# SCH_attempt2_2024-01-23.net
KiCad netlist of a schematic drawn in EasyEDA
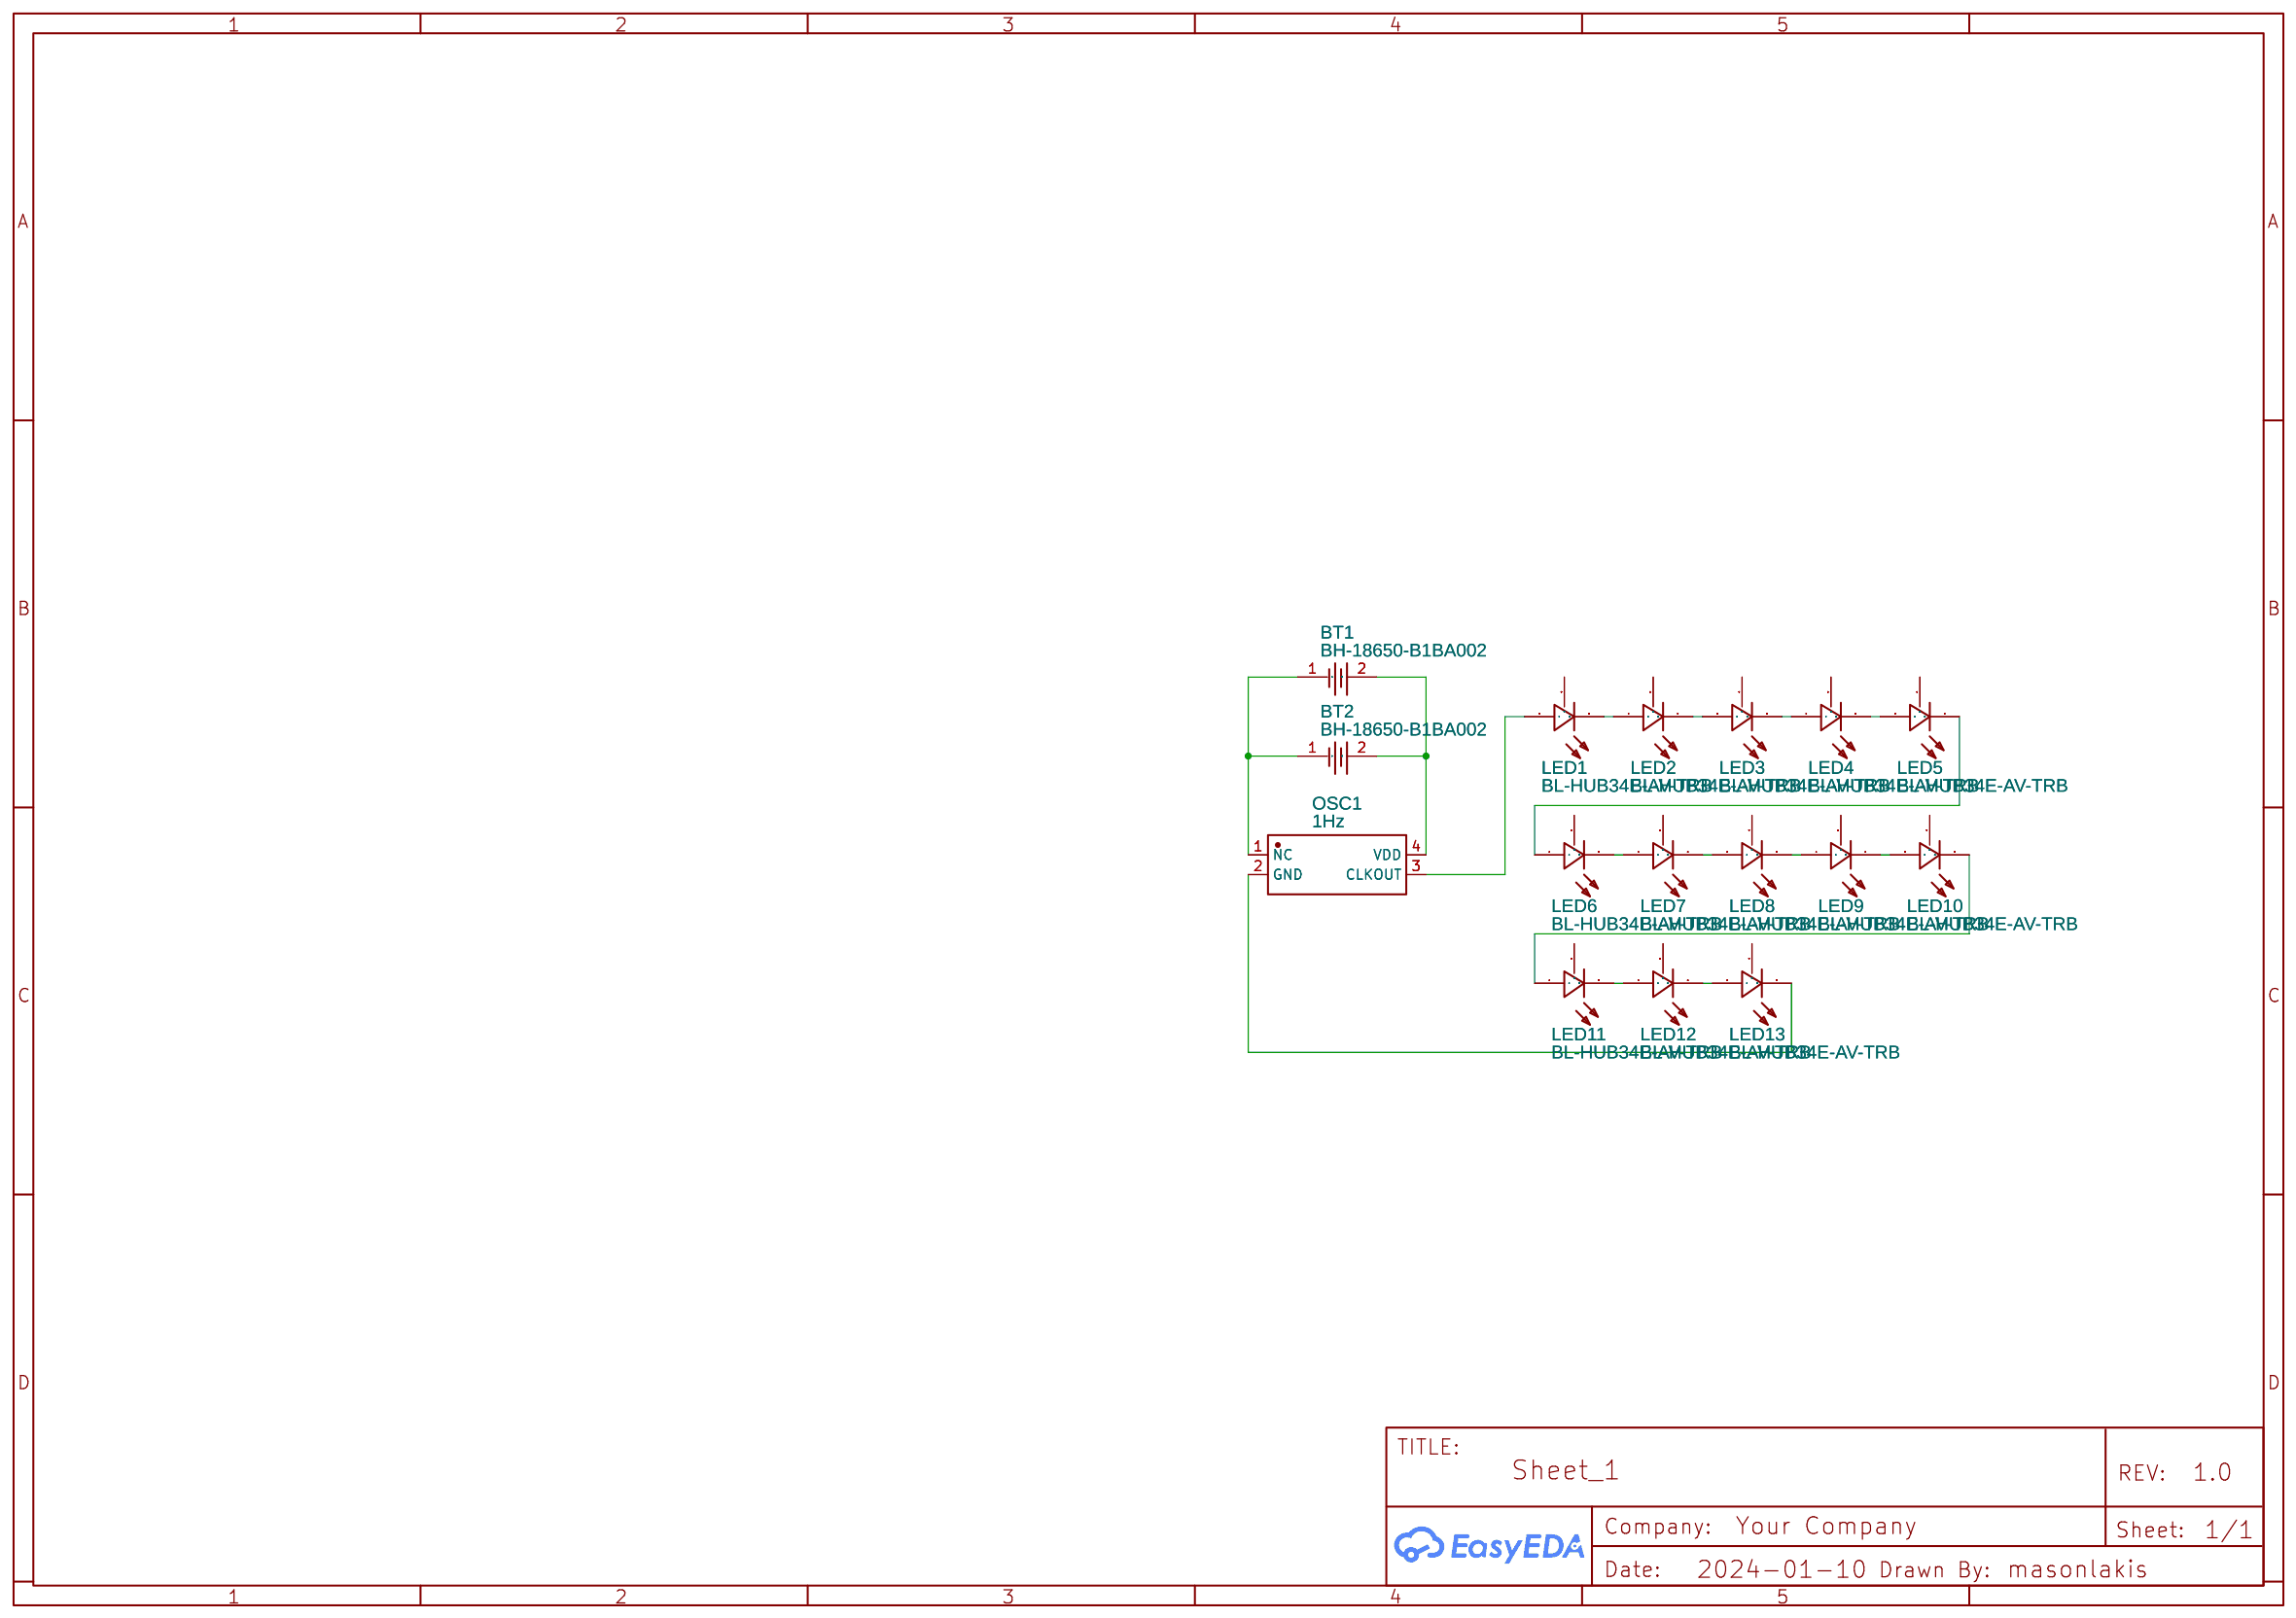
[diagram p0: schematic sheet]

(export (version "E")
  (design (tool "Eeschema 10.0.6"))
  (components
    (comp (ref "BT1")
      (value "BH-18650-B1BA002")
      (fields (field (name "Manufacturer") "MYOUNG(美阳)"))
      (libsource (lib "") (part "BH-18650-B1BA002"))
    )
    (comp (ref "BT2")
      (value "BH-18650-B1BA002")
      (fields (field (name "Manufacturer") "MYOUNG(美阳)"))
      (libsource (lib "") (part "BH-18650-B1BA002"))
    )
    (comp (ref "LED1")
      (value "BL-HUB34E-AV-TRB")
      (fields (field (name "Manufacturer") "BrtLed(佰鸿)"))
      (libsource (lib "") (part "BL-HUB34E-AV-TRB"))
    )
    (comp (ref "LED2")
      (value "BL-HUB34E-AV-TRB")
      (fields (field (name "Manufacturer") "BrtLed(佰鸿)"))
      (libsource (lib "") (part "BL-HUB34E-AV-TRB"))
    )
    (comp (ref "LED3")
      (value "BL-HUB34E-AV-TRB")
      (fields (field (name "Manufacturer") "BrtLed(佰鸿)"))
      (libsource (lib "") (part "BL-HUB34E-AV-TRB"))
    )
    (comp (ref "LED4")
      (value "BL-HUB34E-AV-TRB")
      (fields (field (name "Manufacturer") "BrtLed(佰鸿)"))
      (libsource (lib "") (part "BL-HUB34E-AV-TRB"))
    )
    (comp (ref "LED5")
      (value "BL-HUB34E-AV-TRB")
      (fields (field (name "Manufacturer") "BrtLed(佰鸿)"))
      (libsource (lib "") (part "BL-HUB34E-AV-TRB"))
    )
    (comp (ref "LED6")
      (value "BL-HUB34E-AV-TRB")
      (fields (field (name "Manufacturer") "BrtLed(佰鸿)"))
      (libsource (lib "") (part "BL-HUB34E-AV-TRB"))
    )
    (comp (ref "LED7")
      (value "BL-HUB34E-AV-TRB")
      (fields (field (name "Manufacturer") "BrtLed(佰鸿)"))
      (libsource (lib "") (part "BL-HUB34E-AV-TRB"))
    )
    (comp (ref "LED8")
      (value "BL-HUB34E-AV-TRB")
      (fields (field (name "Manufacturer") "BrtLed(佰鸿)"))
      (libsource (lib "") (part "BL-HUB34E-AV-TRB"))
    )
    (comp (ref "LED9")
      (value "BL-HUB34E-AV-TRB")
      (fields (field (name "Manufacturer") "BrtLed(佰鸿)"))
      (libsource (lib "") (part "BL-HUB34E-AV-TRB"))
    )
    (comp (ref "LED10")
      (value "BL-HUB34E-AV-TRB")
      (fields (field (name "Manufacturer") "BrtLed(佰鸿)"))
      (libsource (lib "") (part "BL-HUB34E-AV-TRB"))
    )
    (comp (ref "LED11")
      (value "BL-HUB34E-AV-TRB")
      (fields (field (name "Manufacturer") "BrtLed(佰鸿)"))
      (libsource (lib "") (part "BL-HUB34E-AV-TRB"))
    )
    (comp (ref "LED12")
      (value "BL-HUB34E-AV-TRB")
      (fields (field (name "Manufacturer") "BrtLed(佰鸿)"))
      (libsource (lib "") (part "BL-HUB34E-AV-TRB"))
    )
    (comp (ref "LED13")
      (value "BL-HUB34E-AV-TRB")
      (fields (field (name "Manufacturer") "BrtLed(佰鸿)"))
      (libsource (lib "") (part "BL-HUB34E-AV-TRB"))
    )
    (comp (ref "OSC1")
      (value "1Hz")
      (fields
        (field (name "Manufacturer Part") "ASTMK-0.001KHZ-LQ-D14-H-T3")
        (field (name "Manufacturer") "ABRACON")
      )
      (libsource (lib "") (part "ASTMK-0.001KHZ-LQ-D14-H-T3"))
    )
  )
  (nets
    (net (code "1") (name "Net-(LED1-A)") (class "Default")
      (node (ref "LED1") (pin "1") (pinfunction "A_1") (pintype "unspecified"))
      (node (ref "OSC1") (pin "3") (pinfunction "CLKOUT_3") (pintype "unspecified"))
    )
    (net (code "2") (name "Net-(LED1-C)") (class "Default")
      (node (ref "LED1") (pin "2") (pinfunction "C_2") (pintype "unspecified"))
      (node (ref "LED2") (pin "1") (pinfunction "A_1") (pintype "unspecified"))
    )
    (net (code "3") (name "Net-(LED2-C)") (class "Default")
      (node (ref "LED2") (pin "2") (pinfunction "C_2") (pintype "unspecified"))
      (node (ref "LED3") (pin "1") (pinfunction "A_1") (pintype "unspecified"))
    )
    (net (code "4") (name "Net-(LED3-C)") (class "Default")
      (node (ref "LED3") (pin "2") (pinfunction "C_2") (pintype "unspecified"))
      (node (ref "LED4") (pin "1") (pinfunction "A_1") (pintype "unspecified"))
    )
    (net (code "5") (name "Net-(LED4-C)") (class "Default")
      (node (ref "LED4") (pin "2") (pinfunction "C_2") (pintype "unspecified"))
      (node (ref "LED5") (pin "1") (pinfunction "A_1") (pintype "unspecified"))
    )
    (net (code "6") (name "Net-(LED5-C)") (class "Default")
      (node (ref "LED5") (pin "2") (pinfunction "C_2") (pintype "unspecified"))
      (node (ref "LED6") (pin "1") (pinfunction "A_1") (pintype "unspecified"))
    )
    (net (code "7") (name "Net-(LED6-C)") (class "Default")
      (node (ref "LED6") (pin "2") (pinfunction "C_2") (pintype "unspecified"))
      (node (ref "LED7") (pin "1") (pinfunction "A_1") (pintype "unspecified"))
    )
    (net (code "8") (name "Net-(LED7-C)") (class "Default")
      (node (ref "LED7") (pin "2") (pinfunction "C_2") (pintype "unspecified"))
      (node (ref "LED8") (pin "1") (pinfunction "A_1") (pintype "unspecified"))
    )
    (net (code "9") (name "Net-(LED8-C)") (class "Default")
      (node (ref "LED8") (pin "2") (pinfunction "C_2") (pintype "unspecified"))
      (node (ref "LED9") (pin "1") (pinfunction "A_1") (pintype "unspecified"))
    )
    (net (code "10") (name "Net-(LED10-A)") (class "Default")
      (node (ref "LED10") (pin "1") (pinfunction "A_1") (pintype "unspecified"))
      (node (ref "LED9") (pin "2") (pinfunction "C_2") (pintype "unspecified"))
    )
    (net (code "11") (name "Net-(LED10-C)") (class "Default")
      (node (ref "LED10") (pin "2") (pinfunction "C_2") (pintype "unspecified"))
      (node (ref "LED11") (pin "1") (pinfunction "A_1") (pintype "unspecified"))
    )
    (net (code "12") (name "Net-(LED11-C)") (class "Default")
      (node (ref "LED11") (pin "2") (pinfunction "C_2") (pintype "unspecified"))
      (node (ref "LED12") (pin "1") (pinfunction "A_1") (pintype "unspecified"))
    )
    (net (code "13") (name "Net-(LED12-C)") (class "Default")
      (node (ref "LED12") (pin "2") (pinfunction "C_2") (pintype "unspecified"))
      (node (ref "LED13") (pin "1") (pinfunction "A_1") (pintype "unspecified"))
    )
    (net (code "14") (name "Net-(LED13-C)") (class "Default")
      (node (ref "LED13") (pin "2") (pinfunction "C_2") (pintype "unspecified"))
      (node (ref "OSC1") (pin "2") (pinfunction "GND_2") (pintype "unspecified"))
    )
    (net (code "15") (name "Net-(OSC1-NC)") (class "Default")
      (node (ref "BT1") (pin "1") (pinfunction "1_1") (pintype "input"))
      (node (ref "BT2") (pin "1") (pinfunction "1_1") (pintype "input"))
      (node (ref "OSC1") (pin "1") (pinfunction "NC_1") (pintype "unspecified"))
    )
    (net (code "16") (name "Net-(OSC1-VDD)") (class "Default")
      (node (ref "BT1") (pin "2") (pinfunction "2_2") (pintype "input"))
      (node (ref "BT2") (pin "2") (pinfunction "2_2") (pintype "input"))
      (node (ref "OSC1") (pin "4") (pinfunction "VDD_4") (pintype "unspecified"))
    )
    (net (code "17") (name "unconnected-(LED1-Pad3)") (class "Default")
      (node (ref "LED1") (pin "3") (pinfunction "3_3") (pintype "unspecified"))
    )
    (net (code "18") (name "unconnected-(LED2-Pad3)") (class "Default")
      (node (ref "LED2") (pin "3") (pinfunction "3_3") (pintype "unspecified"))
    )
    (net (code "19") (name "unconnected-(LED3-Pad3)") (class "Default")
      (node (ref "LED3") (pin "3") (pinfunction "3_3") (pintype "unspecified"))
    )
    (net (code "20") (name "unconnected-(LED4-Pad3)") (class "Default")
      (node (ref "LED4") (pin "3") (pinfunction "3_3") (pintype "unspecified"))
    )
    (net (code "21") (name "unconnected-(LED5-Pad3)") (class "Default")
      (node (ref "LED5") (pin "3") (pinfunction "3_3") (pintype "unspecified"))
    )
    (net (code "22") (name "unconnected-(LED6-Pad3)") (class "Default")
      (node (ref "LED6") (pin "3") (pinfunction "3_3") (pintype "unspecified"))
    )
    (net (code "23") (name "unconnected-(LED7-Pad3)") (class "Default")
      (node (ref "LED7") (pin "3") (pinfunction "3_3") (pintype "unspecified"))
    )
    (net (code "24") (name "unconnected-(LED8-Pad3)") (class "Default")
      (node (ref "LED8") (pin "3") (pinfunction "3_3") (pintype "unspecified"))
    )
    (net (code "25") (name "unconnected-(LED9-Pad3)") (class "Default")
      (node (ref "LED9") (pin "3") (pinfunction "3_3") (pintype "unspecified"))
    )
    (net (code "26") (name "unconnected-(LED10-Pad3)") (class "Default")
      (node (ref "LED10") (pin "3") (pinfunction "3_3") (pintype "unspecified"))
    )
    (net (code "27") (name "unconnected-(LED11-Pad3)") (class "Default")
      (node (ref "LED11") (pin "3") (pinfunction "3_3") (pintype "unspecified"))
    )
    (net (code "28") (name "unconnected-(LED12-Pad3)") (class "Default")
      (node (ref "LED12") (pin "3") (pinfunction "3_3") (pintype "unspecified"))
    )
    (net (code "29") (name "unconnected-(LED13-Pad3)") (class "Default")
      (node (ref "LED13") (pin "3") (pinfunction "3_3") (pintype "unspecified"))
    )
  )
)
